# HABSat2_schematic2302.net
KiCad netlist of a schematic drawn in EasyEDA
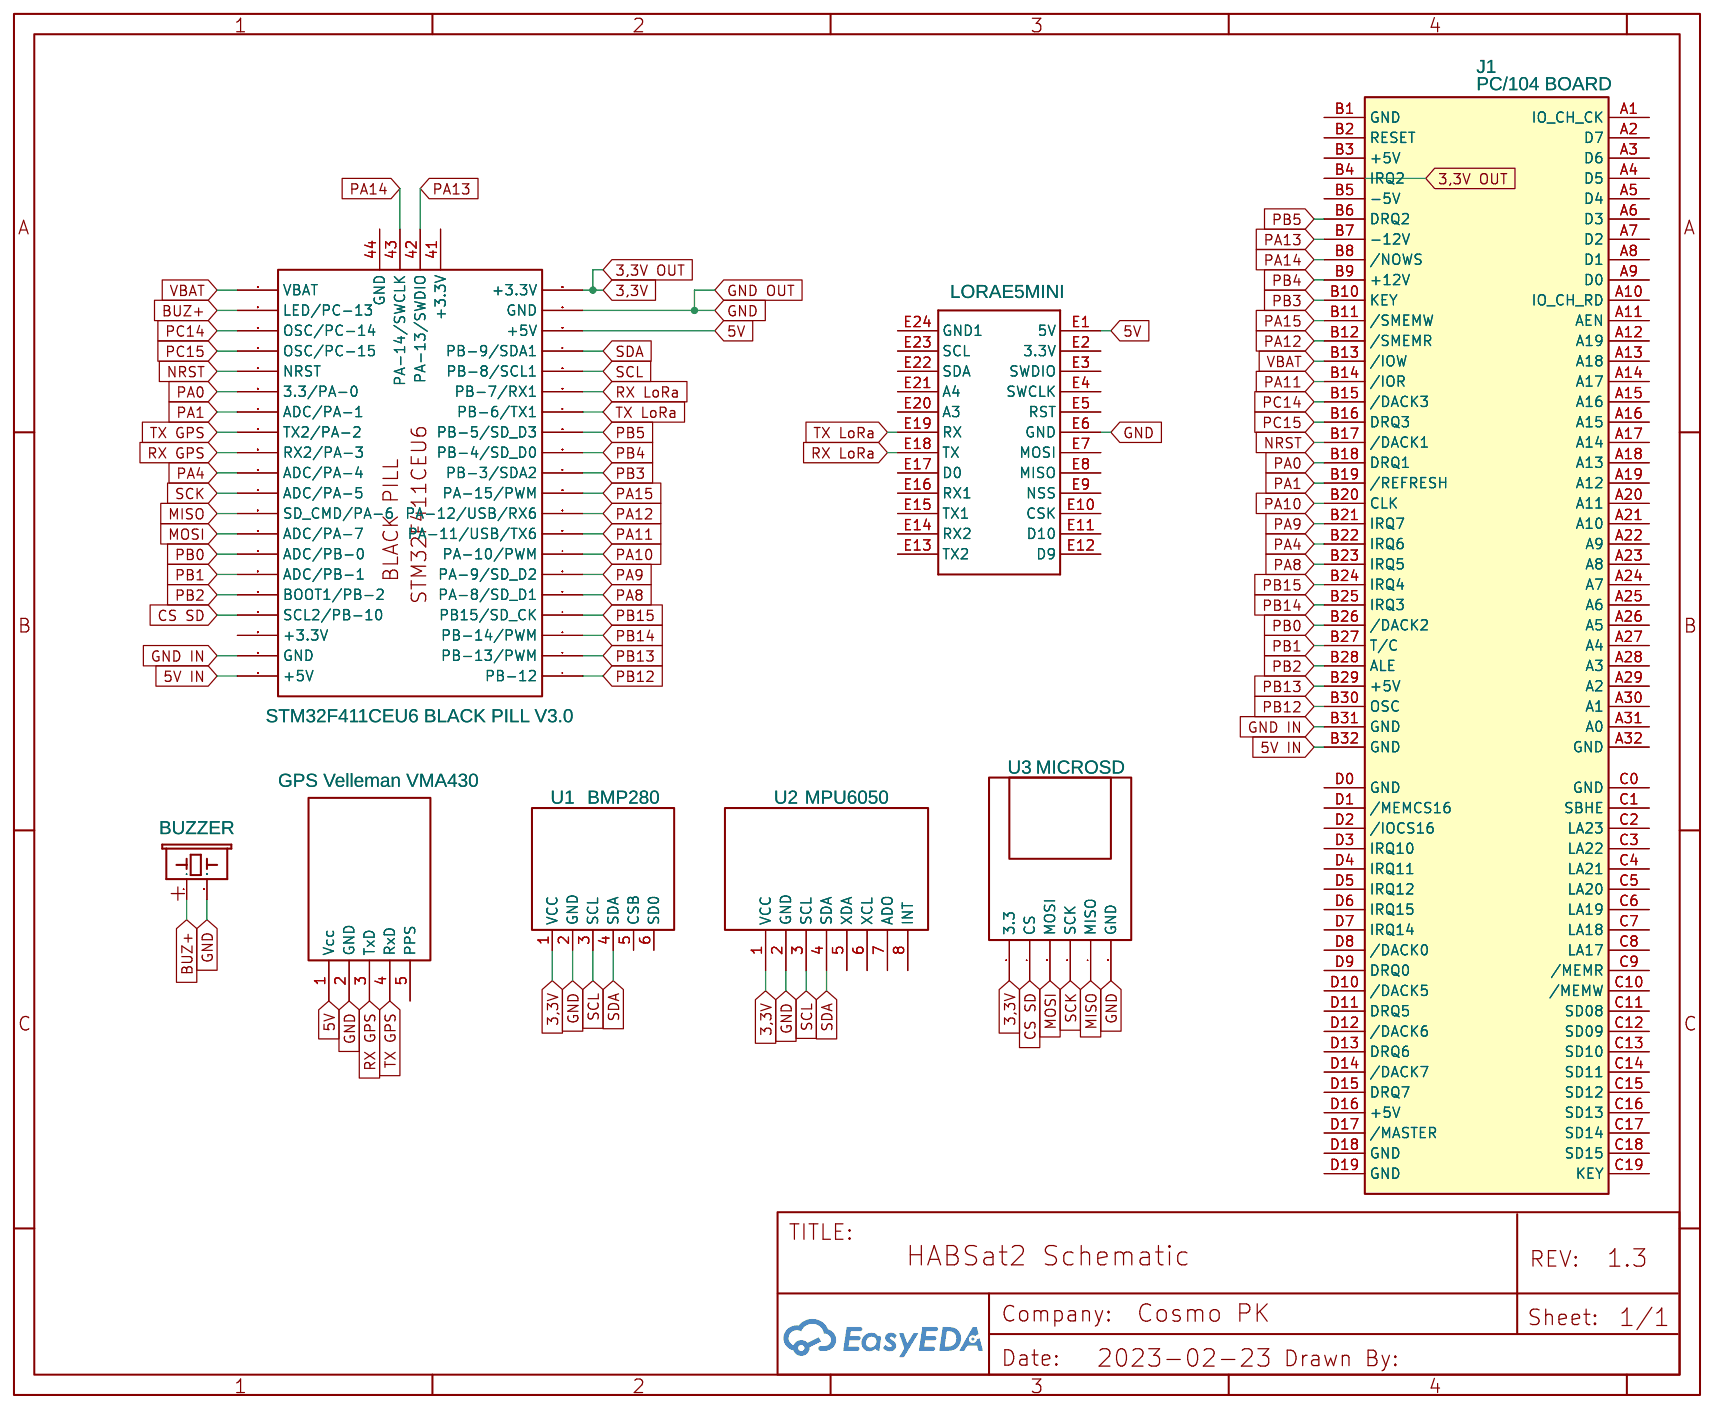
[diagram p0: schematic sheet]

(export (version "E")
  (design (tool "Eeschema 10.0.6"))
  (components
    (comp (ref "1") (value "LORAE5MINI") (libsource (lib "") (part "LORAE5MINI")))
    (comp (ref "J1") (value "PC/104 BOARD") (libsource (lib "") (part "PC/104 BOARD")))
    (comp (ref "SG1") (value "BUZZER") (libsource (lib "") (part "BUZZER KX-12MM")))
    (comp (ref "STM1")
      (value "STM32F411CEU6 BLACK PILL V3.0")
      (libsource (lib "") (part "STM32F411CEU6 BLACK PILL V3.0"))
    )
    (comp (ref "U1")
      (value "BMP280")
      (fields (field (name "BOM_Manufacturer Part") "GY-BMP280"))
      (libsource (lib "") (part "GY-BMP280"))
    )
    (comp (ref "U2") (value "MPU6050") (libsource (lib "") (part "MPU6050")))
    (comp (ref "U3") (value "MICROSD") (libsource (lib "") (part "MICROSD")))
    (comp (ref "VCC")
      (value "GPS Velleman VMA430")
      (fields (field (name "BOM_Manufacturer Part") "VMA430"))
      (libsource (lib "") (part "GPS Velleman VMA430"))
    )
  )
  (nets
    (net (code "1") (name "3,3V") (class "Default")
      (node (ref "J1") (pin "B4") (pinfunction "IRQ2_B4") (pintype "unspecified"))
      (node (ref "STM1") (pin "20") (pinfunction "+3.3V_20") (pintype "unspecified"))
      (node (ref "U1") (pin "1") (pinfunction "VCC_1") (pintype "unspecified"))
      (node (ref "U2") (pin "1") (pinfunction "VCC_1") (pintype "unspecified"))
      (node (ref "U3") (pin "5") (pinfunction "3.3_5") (pintype "unspecified"))
    )
    (net (code "2") (name "5V") (class "Default")
      (node (ref "1") (pin "E1") (pinfunction "5V_E1") (pintype "bidirectional"))
      (node (ref "STM1") (pin "18") (pinfunction "+5V_18") (pintype "unspecified"))
      (node (ref "VCC") (pin "1") (pinfunction "Vcc_1") (pintype "unspecified"))
    )
    (net (code "3") (name "5V IN") (class "Default")
      (node (ref "J1") (pin "B32") (pinfunction "GND_B32") (pintype "bidirectional"))
      (node (ref "STM1") (pin "40") (pinfunction "+5V_40") (pintype "unspecified"))
    )
    (net (code "4") (name "BUZ+") (class "Default")
      (node (ref "SG1") (pin "1") (pinfunction "1_1") (pintype "unspecified"))
      (node (ref "STM1") (pin "22") (pinfunction "LED/PC-13_22") (pintype "unspecified"))
    )
    (net (code "5") (name "CS SD") (class "Default")
      (node (ref "STM1") (pin "37") (pinfunction "SCL2/PB-10_37") (pintype "unspecified"))
      (node (ref "U3") (pin "1") (pinfunction "CS_1") (pintype "unspecified"))
    )
    (net (code "6") (name "GND") (class "Default")
      (node (ref "1") (pin "E6") (pinfunction "GND_E6") (pintype "bidirectional"))
      (node (ref "SG1") (pin "2") (pinfunction "2_2") (pintype "unspecified"))
      (node (ref "STM1") (pin "19") (pinfunction "GND_19") (pintype "unspecified"))
      (node (ref "U1") (pin "2") (pinfunction "GND_2") (pintype "unspecified"))
      (node (ref "U2") (pin "2") (pinfunction "GND_2") (pintype "unspecified"))
      (node (ref "U3") (pin "6") (pinfunction "GND_6") (pintype "unspecified"))
      (node (ref "VCC") (pin "2") (pinfunction "GND_2") (pintype "unspecified"))
    )
    (net (code "7") (name "GND IN") (class "Default")
      (node (ref "J1") (pin "B31") (pinfunction "GND_B31") (pintype "bidirectional"))
      (node (ref "STM1") (pin "39") (pinfunction "GND_39") (pintype "unspecified"))
    )
    (net (code "8") (name "MISO") (class "Default")
      (node (ref "STM1") (pin "32") (pinfunction "SD_CMD/PA-6_32") (pintype "unspecified"))
      (node (ref "U3") (pin "4") (pinfunction "MISO_4") (pintype "unspecified"))
    )
    (net (code "9") (name "MOSI") (class "Default")
      (node (ref "STM1") (pin "33") (pinfunction "ADC/PA-7_33") (pintype "unspecified"))
      (node (ref "U3") (pin "3") (pinfunction "MOSI_3") (pintype "unspecified"))
    )
    (net (code "10") (name "NRST") (class "Default")
      (node (ref "J1") (pin "B17") (pinfunction "/DACK1_B17") (pintype "unspecified"))
      (node (ref "STM1") (pin "25") (pinfunction "NRST_25") (pintype "unspecified"))
    )
    (net (code "11") (name "PA0") (class "Default")
      (node (ref "J1") (pin "B18") (pinfunction "DRQ1_B18") (pintype "unspecified"))
      (node (ref "STM1") (pin "26") (pinfunction "3.3/PA-0_26") (pintype "unspecified"))
    )
    (net (code "12") (name "PA1") (class "Default")
      (node (ref "J1") (pin "B19") (pinfunction "/REFRESH_B19") (pintype "unspecified"))
      (node (ref "STM1") (pin "27") (pinfunction "ADC/PA-1_27") (pintype "unspecified"))
    )
    (net (code "13") (name "PA4") (class "Default")
      (node (ref "J1") (pin "B22") (pinfunction "IRQ6_B22") (pintype "unspecified"))
      (node (ref "STM1") (pin "30") (pinfunction "ADC/PA-4_30") (pintype "unspecified"))
    )
    (net (code "14") (name "PA8") (class "Default")
      (node (ref "J1") (pin "B23") (pinfunction "IRQ5_B23") (pintype "unspecified"))
      (node (ref "STM1") (pin "5") (pinfunction "PA-8/SD_D1_5") (pintype "unspecified"))
    )
    (net (code "15") (name "PA9") (class "Default")
      (node (ref "J1") (pin "B21") (pinfunction "IRQ7_B21") (pintype "unspecified"))
      (node (ref "STM1") (pin "6") (pinfunction "PA-9/SD_D2_6") (pintype "unspecified"))
    )
    (net (code "16") (name "PA10") (class "Default")
      (node (ref "J1") (pin "B20") (pinfunction "CLK_B20") (pintype "output"))
      (node (ref "STM1") (pin "7") (pinfunction "PA-10/PWM_7") (pintype "unspecified"))
    )
    (net (code "17") (name "PA11") (class "Default")
      (node (ref "J1") (pin "B14") (pinfunction "/IOR_B14") (pintype "output"))
      (node (ref "STM1") (pin "8") (pinfunction "PA-11/USB/TX6_8") (pintype "unspecified"))
    )
    (net (code "18") (name "PA12") (class "Default")
      (node (ref "J1") (pin "B12") (pinfunction "/SMEMR_B12") (pintype "output"))
      (node (ref "STM1") (pin "9") (pinfunction "PA-12/USB/RX6_9") (pintype "unspecified"))
    )
    (net (code "19") (name "PA13") (class "Default")
      (node (ref "J1") (pin "B7") (pinfunction "-12V_B7") (pintype "bidirectional"))
      (node (ref "STM1") (pin "42") (pinfunction "PA-13/SWDIO_42") (pintype "unspecified"))
    )
    (net (code "20") (name "PA14") (class "Default")
      (node (ref "J1") (pin "B8") (pinfunction "/NOWS_B8") (pintype "unspecified"))
      (node (ref "STM1") (pin "43") (pinfunction "PA-14/SWCLK_43") (pintype "unspecified"))
    )
    (net (code "21") (name "PA15") (class "Default")
      (node (ref "J1") (pin "B11") (pinfunction "/SMEMW_B11") (pintype "output"))
      (node (ref "STM1") (pin "10") (pinfunction "PA-15/PWM_10") (pintype "unspecified"))
    )
    (net (code "22") (name "PB0") (class "Default")
      (node (ref "J1") (pin "B26") (pinfunction "/DACK2_B26") (pintype "unspecified"))
      (node (ref "STM1") (pin "34") (pinfunction "ADC/PB-0_34") (pintype "unspecified"))
    )
    (net (code "23") (name "PB1") (class "Default")
      (node (ref "J1") (pin "B27") (pinfunction "T/C_B27") (pintype "unspecified"))
      (node (ref "STM1") (pin "35") (pinfunction "ADC/PB-1_35") (pintype "unspecified"))
    )
    (net (code "24") (name "PB2") (class "Default")
      (node (ref "J1") (pin "B28") (pinfunction "ALE_B28") (pintype "output"))
      (node (ref "STM1") (pin "36") (pinfunction "BOOT1/PB-2_36") (pintype "unspecified"))
    )
    (net (code "25") (name "PB3") (class "Default")
      (node (ref "J1") (pin "B10") (pinfunction "KEY_B10") (pintype "bidirectional"))
      (node (ref "STM1") (pin "11") (pinfunction "PB-3/SDA2_11") (pintype "unspecified"))
    )
    (net (code "26") (name "PB4") (class "Default")
      (node (ref "J1") (pin "B9") (pinfunction "+12V_B9") (pintype "bidirectional"))
      (node (ref "STM1") (pin "12") (pinfunction "PB-4/SD_D0_12") (pintype "unspecified"))
    )
    (net (code "27") (name "PB5") (class "Default")
      (node (ref "J1") (pin "B6") (pinfunction "DRQ2_B6") (pintype "unspecified"))
      (node (ref "STM1") (pin "13") (pinfunction "PB-5/SD_D3_13") (pintype "unspecified"))
    )
    (net (code "28") (name "PB12") (class "Default")
      (node (ref "J1") (pin "B30") (pinfunction "OSC_B30") (pintype "output"))
      (node (ref "STM1") (pin "1") (pinfunction "PB-12_1") (pintype "unspecified"))
    )
    (net (code "29") (name "PB13") (class "Default")
      (node (ref "J1") (pin "B29") (pinfunction "+5V_B29") (pintype "bidirectional"))
      (node (ref "STM1") (pin "2") (pinfunction "PB-13/PWM_2") (pintype "unspecified"))
    )
    (net (code "30") (name "PB14") (class "Default")
      (node (ref "J1") (pin "B25") (pinfunction "IRQ3_B25") (pintype "unspecified"))
      (node (ref "STM1") (pin "3") (pinfunction "PB-14/PWM_3") (pintype "unspecified"))
    )
    (net (code "31") (name "PB15") (class "Default")
      (node (ref "J1") (pin "B24") (pinfunction "IRQ4_B24") (pintype "unspecified"))
      (node (ref "STM1") (pin "4") (pinfunction "PB15/SD_CK_4") (pintype "unspecified"))
    )
    (net (code "32") (name "PC14") (class "Default")
      (node (ref "J1") (pin "B15") (pinfunction "/DACK3_B15") (pintype "unspecified"))
      (node (ref "STM1") (pin "23") (pinfunction "OSC/PC-14_23") (pintype "unspecified"))
    )
    (net (code "33") (name "PC15") (class "Default")
      (node (ref "J1") (pin "B16") (pinfunction "DRQ3_B16") (pintype "unspecified"))
      (node (ref "STM1") (pin "24") (pinfunction "OSC/PC-15_24") (pintype "unspecified"))
    )
    (net (code "34") (name "RX GPS") (class "Default")
      (node (ref "STM1") (pin "29") (pinfunction "RX2/PA-3_29") (pintype "unspecified"))
      (node (ref "VCC") (pin "3") (pinfunction "TxD_3") (pintype "unspecified"))
    )
    (net (code "35") (name "RX LoRa") (class "Default")
      (node (ref "1") (pin "E18") (pinfunction "TX_E18") (pintype "bidirectional"))
      (node (ref "STM1") (pin "15") (pinfunction "PB-7/RX1_15") (pintype "unspecified"))
    )
    (net (code "36") (name "SCK") (class "Default")
      (node (ref "STM1") (pin "31") (pinfunction "ADC/PA-5_31") (pintype "unspecified"))
      (node (ref "U3") (pin "2") (pinfunction "SCK_2") (pintype "unspecified"))
    )
    (net (code "37") (name "SCL") (class "Default")
      (node (ref "STM1") (pin "16") (pinfunction "PB-8/SCL1_16") (pintype "unspecified"))
      (node (ref "U1") (pin "3") (pinfunction "SCL_3") (pintype "unspecified"))
      (node (ref "U2") (pin "3") (pinfunction "SCL_3") (pintype "unspecified"))
    )
    (net (code "38") (name "SDA") (class "Default")
      (node (ref "STM1") (pin "17") (pinfunction "PB-9/SDA1_17") (pintype "unspecified"))
      (node (ref "U1") (pin "4") (pinfunction "SDA_4") (pintype "unspecified"))
      (node (ref "U2") (pin "4") (pinfunction "SDA_4") (pintype "unspecified"))
    )
    (net (code "39") (name "TX GPS") (class "Default")
      (node (ref "STM1") (pin "28") (pinfunction "TX2/PA-2_28") (pintype "unspecified"))
      (node (ref "VCC") (pin "4") (pinfunction "RxD_4") (pintype "unspecified"))
    )
    (net (code "40") (name "TX LoRa") (class "Default")
      (node (ref "1") (pin "E19") (pinfunction "RX_E19") (pintype "bidirectional"))
      (node (ref "STM1") (pin "14") (pinfunction "PB-6/TX1_14") (pintype "unspecified"))
    )
    (net (code "41") (name "VBAT") (class "Default")
      (node (ref "J1") (pin "B13") (pinfunction "/IOW_B13") (pintype "output"))
      (node (ref "STM1") (pin "21") (pinfunction "VBAT_21") (pintype "unspecified"))
    )
    (net (code "42") (name "unconnected-(1-3.3V-PadE2)") (class "Default")
      (node (ref "1") (pin "E2") (pinfunction "3.3V_E2") (pintype "bidirectional"))
    )
    (net (code "43") (name "unconnected-(1-A3-PadE20)") (class "Default")
      (node (ref "1") (pin "E20") (pinfunction "A3_E20") (pintype "bidirectional"))
    )
    (net (code "44") (name "unconnected-(1-A4-PadE21)") (class "Default")
      (node (ref "1") (pin "E21") (pinfunction "A4_E21") (pintype "bidirectional"))
    )
    (net (code "45") (name "unconnected-(1-CSK-PadE10)") (class "Default")
      (node (ref "1") (pin "E10") (pinfunction "CSK_E10") (pintype "bidirectional"))
    )
    (net (code "46") (name "unconnected-(1-D0-PadE17)") (class "Default")
      (node (ref "1") (pin "E17") (pinfunction "D0_E17") (pintype "bidirectional"))
    )
    (net (code "47") (name "unconnected-(1-D9-PadE12)") (class "Default")
      (node (ref "1") (pin "E12") (pinfunction "D9_E12") (pintype "bidirectional"))
    )
    (net (code "48") (name "unconnected-(1-D10-PadE11)") (class "Default")
      (node (ref "1") (pin "E11") (pinfunction "D10_E11") (pintype "bidirectional"))
    )
    (net (code "49") (name "unconnected-(1-GND1-PadE24)") (class "Default")
      (node (ref "1") (pin "E24") (pinfunction "GND1_E24") (pintype "bidirectional"))
    )
    (net (code "50") (name "unconnected-(1-MISO-PadE8)") (class "Default")
      (node (ref "1") (pin "E8") (pinfunction "MISO_E8") (pintype "bidirectional"))
    )
    (net (code "51") (name "unconnected-(1-MOSI-PadE7)") (class "Default")
      (node (ref "1") (pin "E7") (pinfunction "MOSI_E7") (pintype "bidirectional"))
    )
    (net (code "52") (name "unconnected-(1-NSS-PadE9)") (class "Default")
      (node (ref "1") (pin "E9") (pinfunction "NSS_E9") (pintype "bidirectional"))
    )
    (net (code "53") (name "unconnected-(1-RST-PadE5)") (class "Default")
      (node (ref "1") (pin "E5") (pinfunction "RST_E5") (pintype "bidirectional"))
    )
    (net (code "54") (name "unconnected-(1-RX1-PadE16)") (class "Default")
      (node (ref "1") (pin "E16") (pinfunction "RX1_E16") (pintype "bidirectional"))
    )
    (net (code "55") (name "unconnected-(1-RX2-PadE14)") (class "Default")
      (node (ref "1") (pin "E14") (pinfunction "RX2_E14") (pintype "bidirectional"))
    )
    (net (code "56") (name "unconnected-(1-SCL-PadE23)") (class "Default")
      (node (ref "1") (pin "E23") (pinfunction "SCL_E23") (pintype "bidirectional"))
    )
    (net (code "57") (name "unconnected-(1-SDA-PadE22)") (class "Default")
      (node (ref "1") (pin "E22") (pinfunction "SDA_E22") (pintype "bidirectional"))
    )
    (net (code "58") (name "unconnected-(1-SWCLK-PadE4)") (class "Default")
      (node (ref "1") (pin "E4") (pinfunction "SWCLK_E4") (pintype "bidirectional"))
    )
    (net (code "59") (name "unconnected-(1-SWDIO-PadE3)") (class "Default")
      (node (ref "1") (pin "E3") (pinfunction "SWDIO_E3") (pintype "bidirectional"))
    )
    (net (code "60") (name "unconnected-(1-TX1-PadE15)") (class "Default")
      (node (ref "1") (pin "E15") (pinfunction "TX1_E15") (pintype "bidirectional"))
    )
    (net (code "61") (name "unconnected-(1-TX2-PadE13)") (class "Default")
      (node (ref "1") (pin "E13") (pinfunction "TX2_E13") (pintype "bidirectional"))
    )
    (net (code "62") (name "unconnected-(J1-+5V-PadB3)") (class "Default")
      (node (ref "J1") (pin "B3") (pinfunction "+5V_B3") (pintype "bidirectional"))
    )
    (net (code "63") (name "unconnected-(J1-+5V-PadD16)") (class "Default")
      (node (ref "J1") (pin "D16") (pinfunction "+5V_D16") (pintype "bidirectional"))
    )
    (net (code "64") (name "unconnected-(J1--5V-PadB5)") (class "Default")
      (node (ref "J1") (pin "B5") (pinfunction "-5V_B5") (pintype "bidirectional"))
    )
    (net (code "65") (name "unconnected-(J1-A0-PadA31)") (class "Default")
      (node (ref "J1") (pin "A31") (pinfunction "A0_A31") (pintype "bidirectional"))
    )
    (net (code "66") (name "unconnected-(J1-A1-PadA30)") (class "Default")
      (node (ref "J1") (pin "A30") (pinfunction "A1_A30") (pintype "bidirectional"))
    )
    (net (code "67") (name "unconnected-(J1-A2-PadA29)") (class "Default")
      (node (ref "J1") (pin "A29") (pinfunction "A2_A29") (pintype "bidirectional"))
    )
    (net (code "68") (name "unconnected-(J1-A3-PadA28)") (class "Default")
      (node (ref "J1") (pin "A28") (pinfunction "A3_A28") (pintype "bidirectional"))
    )
    (net (code "69") (name "unconnected-(J1-A4-PadA27)") (class "Default")
      (node (ref "J1") (pin "A27") (pinfunction "A4_A27") (pintype "bidirectional"))
    )
    (net (code "70") (name "unconnected-(J1-A5-PadA26)") (class "Default")
      (node (ref "J1") (pin "A26") (pinfunction "A5_A26") (pintype "bidirectional"))
    )
    (net (code "71") (name "unconnected-(J1-A6-PadA25)") (class "Default")
      (node (ref "J1") (pin "A25") (pinfunction "A6_A25") (pintype "bidirectional"))
    )
    (net (code "72") (name "unconnected-(J1-A7-PadA24)") (class "Default")
      (node (ref "J1") (pin "A24") (pinfunction "A7_A24") (pintype "bidirectional"))
    )
    (net (code "73") (name "unconnected-(J1-A8-PadA23)") (class "Default")
      (node (ref "J1") (pin "A23") (pinfunction "A8_A23") (pintype "bidirectional"))
    )
    (net (code "74") (name "unconnected-(J1-A9-PadA22)") (class "Default")
      (node (ref "J1") (pin "A22") (pinfunction "A9_A22") (pintype "bidirectional"))
    )
    (net (code "75") (name "unconnected-(J1-A10-PadA21)") (class "Default")
      (node (ref "J1") (pin "A21") (pinfunction "A10_A21") (pintype "bidirectional"))
    )
    (net (code "76") (name "unconnected-(J1-A11-PadA20)") (class "Default")
      (node (ref "J1") (pin "A20") (pinfunction "A11_A20") (pintype "bidirectional"))
    )
    (net (code "77") (name "unconnected-(J1-A12-PadA19)") (class "Default")
      (node (ref "J1") (pin "A19") (pinfunction "A12_A19") (pintype "bidirectional"))
    )
    (net (code "78") (name "unconnected-(J1-A13-PadA18)") (class "Default")
      (node (ref "J1") (pin "A18") (pinfunction "A13_A18") (pintype "bidirectional"))
    )
    (net (code "79") (name "unconnected-(J1-A14-PadA17)") (class "Default")
      (node (ref "J1") (pin "A17") (pinfunction "A14_A17") (pintype "bidirectional"))
    )
    (net (code "80") (name "unconnected-(J1-A15-PadA16)") (class "Default")
      (node (ref "J1") (pin "A16") (pinfunction "A15_A16") (pintype "bidirectional"))
    )
    (net (code "81") (name "unconnected-(J1-A16-PadA15)") (class "Default")
      (node (ref "J1") (pin "A15") (pinfunction "A16_A15") (pintype "bidirectional"))
    )
    (net (code "82") (name "unconnected-(J1-A17-PadA14)") (class "Default")
      (node (ref "J1") (pin "A14") (pinfunction "A17_A14") (pintype "bidirectional"))
    )
    (net (code "83") (name "unconnected-(J1-A18-PadA13)") (class "Default")
      (node (ref "J1") (pin "A13") (pinfunction "A18_A13") (pintype "bidirectional"))
    )
    (net (code "84") (name "unconnected-(J1-A19-PadA12)") (class "Default")
      (node (ref "J1") (pin "A12") (pinfunction "A19_A12") (pintype "bidirectional"))
    )
    (net (code "85") (name "unconnected-(J1-AEN-PadA11)") (class "Default")
      (node (ref "J1") (pin "A11") (pinfunction "AEN_A11") (pintype "output"))
    )
    (net (code "86") (name "unconnected-(J1-D0-PadA9)") (class "Default")
      (node (ref "J1") (pin "A9") (pinfunction "D0_A9") (pintype "bidirectional"))
    )
    (net (code "87") (name "unconnected-(J1-D1-PadA8)") (class "Default")
      (node (ref "J1") (pin "A8") (pinfunction "D1_A8") (pintype "bidirectional"))
    )
    (net (code "88") (name "unconnected-(J1-D2-PadA7)") (class "Default")
      (node (ref "J1") (pin "A7") (pinfunction "D2_A7") (pintype "bidirectional"))
    )
    (net (code "89") (name "unconnected-(J1-D3-PadA6)") (class "Default")
      (node (ref "J1") (pin "A6") (pinfunction "D3_A6") (pintype "bidirectional"))
    )
    (net (code "90") (name "unconnected-(J1-D4-PadA5)") (class "Default")
      (node (ref "J1") (pin "A5") (pinfunction "D4_A5") (pintype "bidirectional"))
    )
    (net (code "91") (name "unconnected-(J1-D5-PadA4)") (class "Default")
      (node (ref "J1") (pin "A4") (pinfunction "D5_A4") (pintype "bidirectional"))
    )
    (net (code "92") (name "unconnected-(J1-D6-PadA3)") (class "Default")
      (node (ref "J1") (pin "A3") (pinfunction "D6_A3") (pintype "bidirectional"))
    )
    (net (code "93") (name "unconnected-(J1-D7-PadA2)") (class "Default")
      (node (ref "J1") (pin "A2") (pinfunction "D7_A2") (pintype "bidirectional"))
    )
    (net (code "94") (name "unconnected-(J1-DRQ0-PadD9)") (class "Default")
      (node (ref "J1") (pin "D9") (pinfunction "DRQ0_D9") (pintype "unspecified"))
    )
    (net (code "95") (name "unconnected-(J1-DRQ5-PadD11)") (class "Default")
      (node (ref "J1") (pin "D11") (pinfunction "DRQ5_D11") (pintype "unspecified"))
    )
    (net (code "96") (name "unconnected-(J1-DRQ6-PadD13)") (class "Default")
      (node (ref "J1") (pin "D13") (pinfunction "DRQ6_D13") (pintype "unspecified"))
    )
    (net (code "97") (name "unconnected-(J1-DRQ7-PadD15)") (class "Default")
      (node (ref "J1") (pin "D15") (pinfunction "DRQ7_D15") (pintype "unspecified"))
    )
    (net (code "98") (name "unconnected-(J1-GND-PadA32)") (class "Default")
      (node (ref "J1") (pin "A32") (pinfunction "GND_A32") (pintype "bidirectional"))
    )
    (net (code "99") (name "unconnected-(J1-GND-PadB1)") (class "Default")
      (node (ref "J1") (pin "B1") (pinfunction "GND_B1") (pintype "bidirectional"))
    )
    (net (code "100") (name "unconnected-(J1-GND-PadC0)") (class "Default")
      (node (ref "J1") (pin "C0") (pinfunction "GND_C0") (pintype "unspecified"))
    )
    (net (code "101") (name "unconnected-(J1-GND-PadD0)") (class "Default")
      (node (ref "J1") (pin "D0") (pinfunction "GND_D0") (pintype "unspecified"))
    )
    (net (code "102") (name "unconnected-(J1-GND-PadD18)") (class "Default")
      (node (ref "J1") (pin "D18") (pinfunction "GND_D18") (pintype "bidirectional"))
    )
    (net (code "103") (name "unconnected-(J1-GND-PadD19)") (class "Default")
      (node (ref "J1") (pin "D19") (pinfunction "GND_D19") (pintype "bidirectional"))
    )
    (net (code "104") (name "unconnected-(J1-IO_CH_CK-PadA1)") (class "Default")
      (node (ref "J1") (pin "A1") (pinfunction "IO_CH_CK_A1") (pintype "unspecified"))
    )
    (net (code "105") (name "unconnected-(J1-IO_CH_RD-PadA10)") (class "Default")
      (node (ref "J1") (pin "A10") (pinfunction "IO_CH_RD_A10") (pintype "unspecified"))
    )
    (net (code "106") (name "unconnected-(J1-IRQ10-PadD3)") (class "Default")
      (node (ref "J1") (pin "D3") (pinfunction "IRQ10_D3") (pintype "unspecified"))
    )
    (net (code "107") (name "unconnected-(J1-IRQ11-PadD4)") (class "Default")
      (node (ref "J1") (pin "D4") (pinfunction "IRQ11_D4") (pintype "unspecified"))
    )
    (net (code "108") (name "unconnected-(J1-IRQ12-PadD5)") (class "Default")
      (node (ref "J1") (pin "D5") (pinfunction "IRQ12_D5") (pintype "unspecified"))
    )
    (net (code "109") (name "unconnected-(J1-IRQ14-PadD7)") (class "Default")
      (node (ref "J1") (pin "D7") (pinfunction "IRQ14_D7") (pintype "unspecified"))
    )
    (net (code "110") (name "unconnected-(J1-IRQ15-PadD6)") (class "Default")
      (node (ref "J1") (pin "D6") (pinfunction "IRQ15_D6") (pintype "unspecified"))
    )
    (net (code "111") (name "unconnected-(J1-KEY-PadC19)") (class "Default")
      (node (ref "J1") (pin "C19") (pinfunction "KEY_C19") (pintype "bidirectional"))
    )
    (net (code "112") (name "unconnected-(J1-LA17-PadC8)") (class "Default")
      (node (ref "J1") (pin "C8") (pinfunction "LA17_C8") (pintype "unspecified"))
    )
    (net (code "113") (name "unconnected-(J1-LA18-PadC7)") (class "Default")
      (node (ref "J1") (pin "C7") (pinfunction "LA18_C7") (pintype "unspecified"))
    )
    (net (code "114") (name "unconnected-(J1-LA19-PadC6)") (class "Default")
      (node (ref "J1") (pin "C6") (pinfunction "LA19_C6") (pintype "unspecified"))
    )
    (net (code "115") (name "unconnected-(J1-LA20-PadC5)") (class "Default")
      (node (ref "J1") (pin "C5") (pinfunction "LA20_C5") (pintype "unspecified"))
    )
    (net (code "116") (name "unconnected-(J1-LA21-PadC4)") (class "Default")
      (node (ref "J1") (pin "C4") (pinfunction "LA21_C4") (pintype "unspecified"))
    )
    (net (code "117") (name "unconnected-(J1-LA22-PadC3)") (class "Default")
      (node (ref "J1") (pin "C3") (pinfunction "LA22_C3") (pintype "unspecified"))
    )
    (net (code "118") (name "unconnected-(J1-LA23-PadC2)") (class "Default")
      (node (ref "J1") (pin "C2") (pinfunction "LA23_C2") (pintype "unspecified"))
    )
    (net (code "119") (name "unconnected-(J1-RESET-PadB2)") (class "Default")
      (node (ref "J1") (pin "B2") (pinfunction "RESET_B2") (pintype "output"))
    )
    (net (code "120") (name "unconnected-(J1-SBHE-PadC1)") (class "Default")
      (node (ref "J1") (pin "C1") (pinfunction "SBHE_C1") (pintype "unspecified"))
    )
    (net (code "121") (name "unconnected-(J1-SD08-PadC11)") (class "Default")
      (node (ref "J1") (pin "C11") (pinfunction "SD08_C11") (pintype "bidirectional"))
    )
    (net (code "122") (name "unconnected-(J1-SD09-PadC12)") (class "Default")
      (node (ref "J1") (pin "C12") (pinfunction "SD09_C12") (pintype "bidirectional"))
    )
    (net (code "123") (name "unconnected-(J1-SD10-PadC13)") (class "Default")
      (node (ref "J1") (pin "C13") (pinfunction "SD10_C13") (pintype "bidirectional"))
    )
    (net (code "124") (name "unconnected-(J1-SD11-PadC14)") (class "Default")
      (node (ref "J1") (pin "C14") (pinfunction "SD11_C14") (pintype "bidirectional"))
    )
    (net (code "125") (name "unconnected-(J1-SD12-PadC15)") (class "Default")
      (node (ref "J1") (pin "C15") (pinfunction "SD12_C15") (pintype "bidirectional"))
    )
    (net (code "126") (name "unconnected-(J1-SD13-PadC16)") (class "Default")
      (node (ref "J1") (pin "C16") (pinfunction "SD13_C16") (pintype "bidirectional"))
    )
    (net (code "127") (name "unconnected-(J1-SD14-PadC17)") (class "Default")
      (node (ref "J1") (pin "C17") (pinfunction "SD14_C17") (pintype "bidirectional"))
    )
    (net (code "128") (name "unconnected-(J1-SD15-PadC18)") (class "Default")
      (node (ref "J1") (pin "C18") (pinfunction "SD15_C18") (pintype "bidirectional"))
    )
    (net (code "129") (name "unconnected-(J1-{slash}DACK0-PadD8)") (class "Default")
      (node (ref "J1") (pin "D8") (pinfunction "/DACK0_D8") (pintype "output"))
    )
    (net (code "130") (name "unconnected-(J1-{slash}DACK5-PadD10)") (class "Default")
      (node (ref "J1") (pin "D10") (pinfunction "/DACK5_D10") (pintype "output"))
    )
    (net (code "131") (name "unconnected-(J1-{slash}DACK6-PadD12)") (class "Default")
      (node (ref "J1") (pin "D12") (pinfunction "/DACK6_D12") (pintype "output"))
    )
    (net (code "132") (name "unconnected-(J1-{slash}DACK7-PadD14)") (class "Default")
      (node (ref "J1") (pin "D14") (pinfunction "/DACK7_D14") (pintype "output"))
    )
    (net (code "133") (name "unconnected-(J1-{slash}IOCS16-PadD2)") (class "Default")
      (node (ref "J1") (pin "D2") (pinfunction "/IOCS16_D2") (pintype "unspecified"))
    )
    (net (code "134") (name "unconnected-(J1-{slash}MASTER-PadD17)") (class "Default")
      (node (ref "J1") (pin "D17") (pinfunction "/MASTER_D17") (pintype "unspecified"))
    )
    (net (code "135") (name "unconnected-(J1-{slash}MEMCS16-PadD1)") (class "Default")
      (node (ref "J1") (pin "D1") (pinfunction "/MEMCS16_D1") (pintype "unspecified"))
    )
    (net (code "136") (name "unconnected-(J1-{slash}MEMR-PadC9)") (class "Default")
      (node (ref "J1") (pin "C9") (pinfunction "/MEMR_C9") (pintype "output"))
    )
    (net (code "137") (name "unconnected-(J1-{slash}MEMW-PadC10)") (class "Default")
      (node (ref "J1") (pin "C10") (pinfunction "/MEMW_C10") (pintype "output"))
    )
    (net (code "138") (name "unconnected-(STM1-+3.3V-Pad38)") (class "Default")
      (node (ref "STM1") (pin "38") (pinfunction "+3.3V_38") (pintype "unspecified"))
    )
    (net (code "139") (name "unconnected-(STM1-+3.3V-Pad41)") (class "Default")
      (node (ref "STM1") (pin "41") (pinfunction "+3.3V_41") (pintype "unspecified"))
    )
    (net (code "140") (name "unconnected-(STM1-GND-Pad44)") (class "Default")
      (node (ref "STM1") (pin "44") (pinfunction "GND_44") (pintype "unspecified"))
    )
    (net (code "141") (name "unconnected-(U1-CSB-Pad5)") (class "Default")
      (node (ref "U1") (pin "5") (pinfunction "CSB_5") (pintype "unspecified"))
    )
    (net (code "142") (name "unconnected-(U1-SD0-Pad6)") (class "Default")
      (node (ref "U1") (pin "6") (pinfunction "SD0_6") (pintype "unspecified"))
    )
    (net (code "143") (name "unconnected-(U2-ADO-Pad7)") (class "Default")
      (node (ref "U2") (pin "7") (pinfunction "ADO_7") (pintype "unspecified"))
    )
    (net (code "144") (name "unconnected-(U2-INT-Pad8)") (class "Default")
      (node (ref "U2") (pin "8") (pinfunction "INT_8") (pintype "unspecified"))
    )
    (net (code "145") (name "unconnected-(U2-XCL-Pad6)") (class "Default")
      (node (ref "U2") (pin "6") (pinfunction "XCL_6") (pintype "unspecified"))
    )
    (net (code "146") (name "unconnected-(U2-XDA-Pad5)") (class "Default")
      (node (ref "U2") (pin "5") (pinfunction "XDA_5") (pintype "unspecified"))
    )
    (net (code "147") (name "unconnected-(VCC-PPS-Pad5)") (class "Default")
      (node (ref "VCC") (pin "5") (pinfunction "PPS_5") (pintype "unspecified"))
    )
  )
)
